# Sensor.net
KiCad netlist of a schematic drawn in Altium Designer
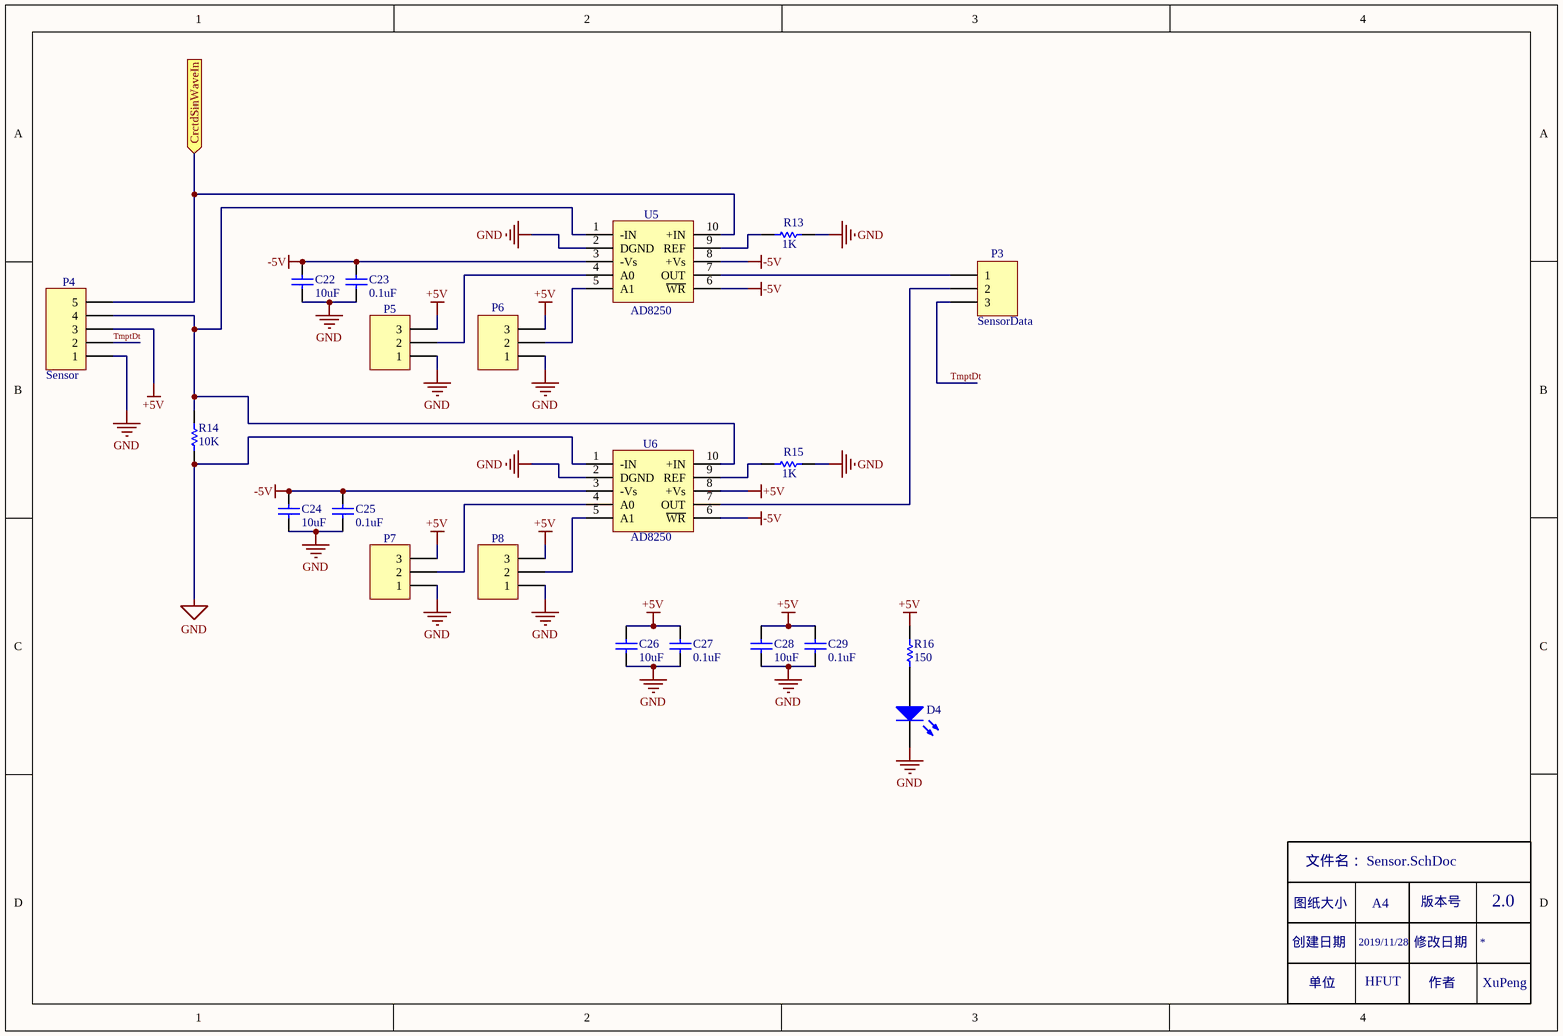
[diagram p0: Sensor.SchDoc]

(export (version "E")
  (design (tool "Eeschema 10.0.6"))
  (components
    (comp (ref "C22")
      (value "10uF")
      (footprint "RB0.1/0.2")
      (description "无极性电容")
      (fields (field (name "Comment") "Cap") (field (name "PUBLISHER") "Altium Limited"))
      (libsource (lib "Fszhang") (part "Cap"))
    )
    (comp (ref "C23")
      (value "0.1uF")
      (footprint "C-RAD")
      (description "无极性电容")
      (fields (field (name "Comment") "Cap") (field (name "PUBLISHER") "Altium Limited"))
      (libsource (lib "Fszhang") (part "Cap"))
    )
    (comp (ref "C24")
      (value "10uF")
      (footprint "RB0.1/0.2")
      (description "无极性电容")
      (fields (field (name "Comment") "Cap") (field (name "PUBLISHER") "Altium Limited"))
      (libsource (lib "Fszhang") (part "Cap"))
    )
    (comp (ref "C25")
      (value "0.1uF")
      (footprint "C-RAD")
      (description "无极性电容")
      (fields (field (name "Comment") "Cap") (field (name "PUBLISHER") "Altium Limited"))
      (libsource (lib "Fszhang") (part "Cap"))
    )
    (comp (ref "C26")
      (value "10uF")
      (footprint "RB0.1/0.2")
      (description "无极性电容")
      (fields (field (name "Comment") "Cap") (field (name "PUBLISHER") "Altium Limited"))
      (libsource (lib "Fszhang") (part "Cap"))
    )
    (comp (ref "C27")
      (value "0.1uF")
      (footprint "C-RAD")
      (description "无极性电容")
      (fields (field (name "Comment") "Cap") (field (name "PUBLISHER") "Altium Limited"))
      (libsource (lib "Fszhang") (part "Cap"))
    )
    (comp (ref "C28")
      (value "10uF")
      (footprint "RB0.1/0.2")
      (description "无极性电容")
      (fields (field (name "Comment") "Cap") (field (name "PUBLISHER") "Altium Limited"))
      (libsource (lib "Fszhang") (part "Cap"))
    )
    (comp (ref "C29")
      (value "0.1uF")
      (footprint "C-RAD")
      (description "无极性电容")
      (fields (field (name "Comment") "Cap") (field (name "PUBLISHER") "Altium Limited"))
      (libsource (lib "Fszhang") (part "Cap"))
    )
    (comp (ref "D4")
      (value "LED0")
      (footprint "RB2.54/4")
      (description "Typical INFRARED GaAs LED")
      (fields (field (name "PUBLISHER") "Altium Limited"))
      (libsource (lib "Miscellaneous Devices") (part "LED0"))
    )
    (comp (ref "P3")
      (value "SensorData")
      (footprint "HDR1X3")
      (description "Header, 3-Pin")
      (fields (field (name "PUBLISHER") "Altium Limited"))
      (libsource (lib "") (part "Header 3_1"))
    )
    (comp (ref "P4")
      (value "Sensor")
      (footprint "HDR1X5")
      (description "Header, 5-Pin")
      (fields (field (name "PUBLISHER") "Altium Limited"))
      (libsource (lib "Miscellaneous Connectors") (part "Header 5"))
    )
    (comp (ref "P5")
      (value "Header 3")
      (footprint "HDR1X3")
      (description "Header, 3-Pin")
      (fields (field (name "PUBLISHER") "Altium Limited"))
      (libsource (lib "Miscellaneous Connectors") (part "Header 3"))
    )
    (comp (ref "P6")
      (value "Header 3")
      (footprint "HDR1X3")
      (description "Header, 3-Pin")
      (fields (field (name "PUBLISHER") "Altium Limited"))
      (libsource (lib "Miscellaneous Connectors") (part "Header 3"))
    )
    (comp (ref "P7")
      (value "Header 3")
      (footprint "HDR1X3")
      (description "Header, 3-Pin")
      (fields (field (name "PUBLISHER") "Altium Limited"))
      (libsource (lib "Miscellaneous Connectors") (part "Header 3"))
    )
    (comp (ref "P8")
      (value "Header 3")
      (footprint "HDR1X3")
      (description "Header, 3-Pin")
      (fields (field (name "PUBLISHER") "Altium Limited"))
      (libsource (lib "Miscellaneous Connectors") (part "Header 3"))
    )
    (comp (ref "R13")
      (value "1K")
      (footprint "AXIAL-0.3")
      (description "Resistor")
      (fields (field (name "Comment") "Res1") (field (name "PUBLISHER") "Altium Limited"))
      (libsource (lib "Miscellaneous Devices") (part "Res1"))
    )
    (comp (ref "R14")
      (value "10K")
      (footprint "AXIAL-0.3")
      (description "Resistor")
      (fields (field (name "Comment") "Res1") (field (name "PUBLISHER") "Altium Limited"))
      (libsource (lib "Miscellaneous Devices") (part "Res1"))
    )
    (comp (ref "R15")
      (value "1K")
      (footprint "AXIAL-0.3")
      (description "Resistor")
      (fields (field (name "Comment") "Res1") (field (name "PUBLISHER") "Altium Limited"))
      (libsource (lib "Miscellaneous Devices") (part "Res1"))
    )
    (comp (ref "R16")
      (value "150")
      (footprint "AXIAL-0.3")
      (description "Resistor")
      (fields (field (name "Comment") "Res1") (field (name "PUBLISHER") "Altium Limited"))
      (libsource (lib "Miscellaneous Devices") (part "Res1"))
    )
    (comp (ref "U5")
      (value "AD8250")
      (footprint "MSOP10")
      (libsource (lib "ElectricalConductivityMeterIntLib") (part "AD8250"))
    )
    (comp (ref "U6")
      (value "AD8250")
      (footprint "MSOP10")
      (libsource (lib "ElectricalConductivityMeterIntLib") (part "AD8250"))
    )
  )
  (nets
    (net (code "1") (name "+5V") (class "Default")
      (node (ref "C26") (pin "2") (pinfunction "2_2") (pintype "passive"))
      (node (ref "C27") (pin "2") (pinfunction "2_2") (pintype "passive"))
      (node (ref "C28") (pin "2") (pinfunction "2_2") (pintype "passive"))
      (node (ref "C29") (pin "2") (pinfunction "2_2") (pintype "passive"))
      (node (ref "P4") (pin "3") (pinfunction "3_3") (pintype "passive"))
      (node (ref "P5") (pin "3") (pinfunction "3_3") (pintype "passive"))
      (node (ref "P6") (pin "3") (pinfunction "3_3") (pintype "passive"))
      (node (ref "P7") (pin "3") (pinfunction "3_3") (pintype "passive"))
      (node (ref "P8") (pin "3") (pinfunction "3_3") (pintype "passive"))
      (node (ref "R16") (pin "2") (pinfunction "2_2") (pintype "passive"))
      (node (ref "U6") (pin "8") (pinfunction "+Vs_8") (pintype "passive"))
    )
    (net (code "2") (name "-5V") (class "Default")
      (node (ref "C22") (pin "2") (pinfunction "2_2") (pintype "passive"))
      (node (ref "C23") (pin "2") (pinfunction "2_2") (pintype "passive"))
      (node (ref "C24") (pin "2") (pinfunction "2_2") (pintype "passive"))
      (node (ref "C25") (pin "2") (pinfunction "2_2") (pintype "passive"))
      (node (ref "U5") (pin "3") (pinfunction "-Vs_3") (pintype "passive"))
      (node (ref "U5") (pin "6") (pinfunction "~{WR}_6") (pintype "passive"))
      (node (ref "U5") (pin "8") (pinfunction "+Vs_8") (pintype "passive"))
      (node (ref "U6") (pin "3") (pinfunction "-Vs_3") (pintype "passive"))
      (node (ref "U6") (pin "6") (pinfunction "~{WR}_6") (pintype "passive"))
    )
    (net (code "3") (name "/CrctdSinWaveIn") (class "Default")
      (node (ref "P4") (pin "5") (pinfunction "5_5") (pintype "passive"))
      (node (ref "U5") (pin "10") (pinfunction "+IN_10") (pintype "passive"))
    )
    (net (code "4") (name "/TmptDt") (class "Default")
      (node (ref "P3") (pin "3") (pinfunction "3_3") (pintype "passive"))
      (node (ref "P4") (pin "2") (pinfunction "2_2") (pintype "passive"))
    )
    (net (code "5") (name "GND") (class "Default")
      (node (ref "C22") (pin "1") (pinfunction "1_1") (pintype "passive"))
      (node (ref "C23") (pin "1") (pinfunction "1_1") (pintype "passive"))
      (node (ref "C24") (pin "1") (pinfunction "1_1") (pintype "passive"))
      (node (ref "C25") (pin "1") (pinfunction "1_1") (pintype "passive"))
      (node (ref "C26") (pin "1") (pinfunction "1_1") (pintype "passive"))
      (node (ref "C27") (pin "1") (pinfunction "1_1") (pintype "passive"))
      (node (ref "C28") (pin "1") (pinfunction "1_1") (pintype "passive"))
      (node (ref "C29") (pin "1") (pinfunction "1_1") (pintype "passive"))
      (node (ref "D4") (pin "2") (pinfunction "K_2") (pintype "passive"))
      (node (ref "P4") (pin "1") (pinfunction "1_1") (pintype "passive"))
      (node (ref "P5") (pin "1") (pinfunction "1_1") (pintype "passive"))
      (node (ref "P6") (pin "1") (pinfunction "1_1") (pintype "passive"))
      (node (ref "P7") (pin "1") (pinfunction "1_1") (pintype "passive"))
      (node (ref "P8") (pin "1") (pinfunction "1_1") (pintype "passive"))
      (node (ref "R13") (pin "2") (pinfunction "2_2") (pintype "passive"))
      (node (ref "R14") (pin "1") (pinfunction "1_1") (pintype "passive"))
      (node (ref "R15") (pin "2") (pinfunction "2_2") (pintype "passive"))
      (node (ref "U5") (pin "2") (pinfunction "DGND_2") (pintype "passive"))
      (node (ref "U6") (pin "1") (pinfunction "-IN_1") (pintype "passive"))
      (node (ref "U6") (pin "2") (pinfunction "DGND_2") (pintype "passive"))
    )
    (net (code "6") (name "Net-(D4-A)") (class "Default")
      (node (ref "D4") (pin "1") (pinfunction "A_1") (pintype "passive"))
      (node (ref "R16") (pin "1") (pinfunction "1_1") (pintype "passive"))
    )
    (net (code "7") (name "Net-(U5--IN)") (class "Default")
      (node (ref "P4") (pin "4") (pinfunction "4_4") (pintype "passive"))
      (node (ref "R14") (pin "2") (pinfunction "2_2") (pintype "passive"))
      (node (ref "U5") (pin "1") (pinfunction "-IN_1") (pintype "passive"))
      (node (ref "U6") (pin "10") (pinfunction "+IN_10") (pintype "passive"))
    )
    (net (code "8") (name "Net-(U5-A0)") (class "Default")
      (node (ref "P5") (pin "2") (pinfunction "2_2") (pintype "passive"))
      (node (ref "U5") (pin "4") (pinfunction "A0_4") (pintype "passive"))
    )
    (net (code "9") (name "Net-(U5-A1)") (class "Default")
      (node (ref "P6") (pin "2") (pinfunction "2_2") (pintype "passive"))
      (node (ref "U5") (pin "5") (pinfunction "A1_5") (pintype "passive"))
    )
    (net (code "10") (name "Net-(U5-OUT)") (class "Default")
      (node (ref "P3") (pin "1") (pinfunction "1_1") (pintype "passive"))
      (node (ref "U5") (pin "7") (pinfunction "OUT_7") (pintype "passive"))
    )
    (net (code "11") (name "Net-(U5-REF)") (class "Default")
      (node (ref "R13") (pin "1") (pinfunction "1_1") (pintype "passive"))
      (node (ref "U5") (pin "9") (pinfunction "REF_9") (pintype "passive"))
    )
    (net (code "12") (name "Net-(U6-A0)") (class "Default")
      (node (ref "P7") (pin "2") (pinfunction "2_2") (pintype "passive"))
      (node (ref "U6") (pin "4") (pinfunction "A0_4") (pintype "passive"))
    )
    (net (code "13") (name "Net-(U6-A1)") (class "Default")
      (node (ref "P8") (pin "2") (pinfunction "2_2") (pintype "passive"))
      (node (ref "U6") (pin "5") (pinfunction "A1_5") (pintype "passive"))
    )
    (net (code "14") (name "Net-(U6-OUT)") (class "Default")
      (node (ref "P3") (pin "2") (pinfunction "2_2") (pintype "passive"))
      (node (ref "U6") (pin "7") (pinfunction "OUT_7") (pintype "passive"))
    )
    (net (code "15") (name "Net-(U6-REF)") (class "Default")
      (node (ref "R15") (pin "1") (pinfunction "1_1") (pintype "passive"))
      (node (ref "U6") (pin "9") (pinfunction "REF_9") (pintype "passive"))
    )
  )
)
